# ATmegaBootloader.net
KiCad netlist of a schematic drawn in EAGLE
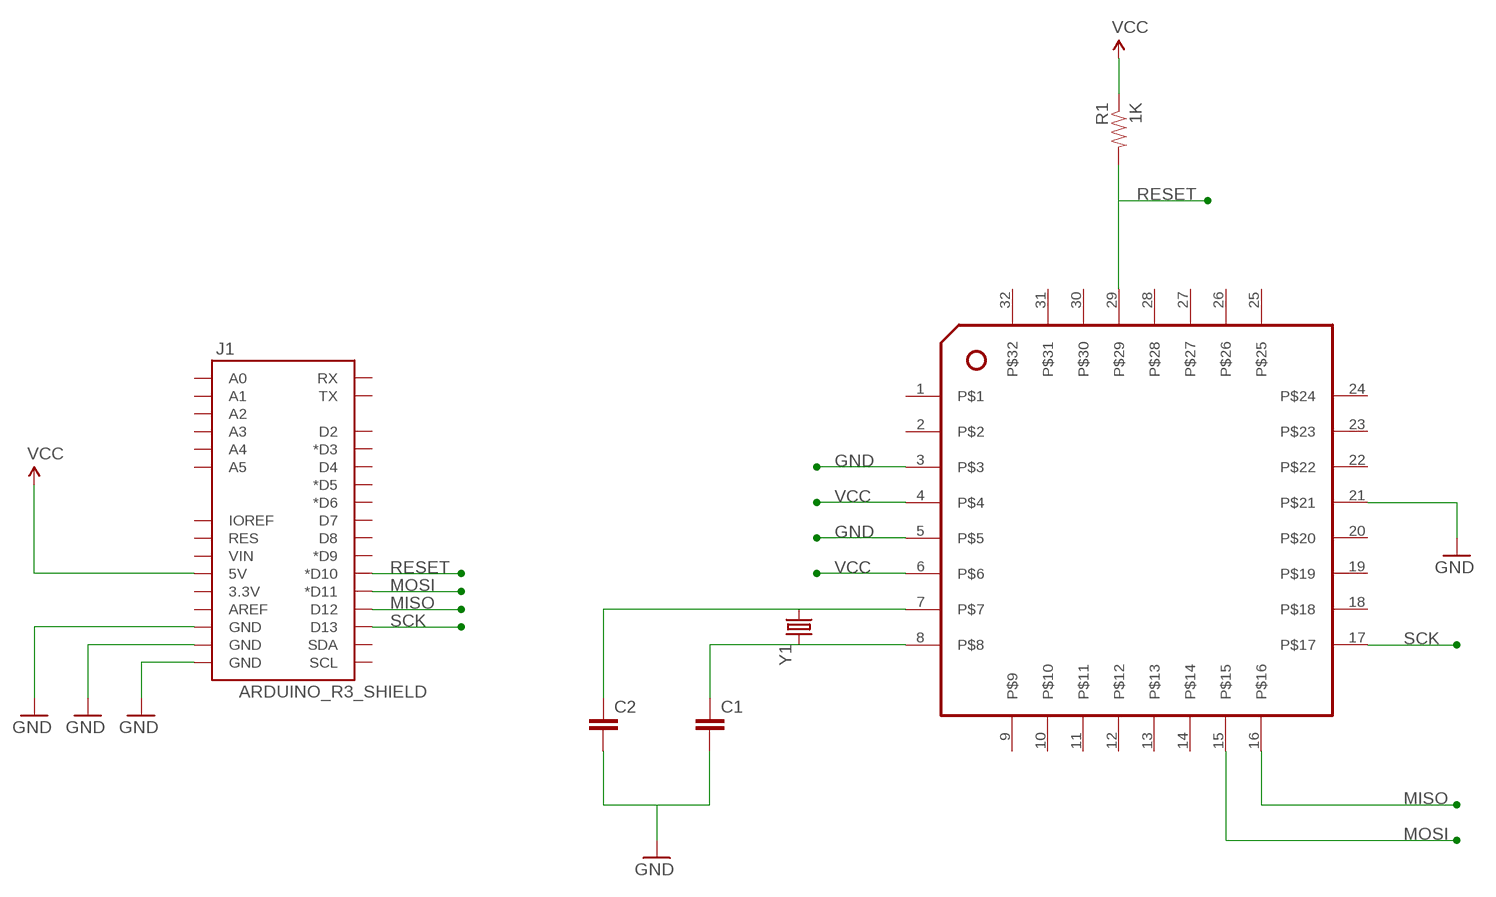
[diagram p0: schematic, sheet 1]

(export (version "E")
  (design (tool "Eeschema 10.0.6"))
  (components
    (comp (ref "C1")
      (value "0.1UF-50V-20%(PTH)KIT-EZ")
      (footprint "eagle-import:CAP-PTH-SMALL-KIT")
      (libsource (lib "eagle-import") (part "0.1UF-50V-20%(PTH)KIT-EZ"))
    )
    (comp (ref "C2")
      (value "0.1UF-50V-20%(PTH)KIT-EZ")
      (footprint "eagle-import:CAP-PTH-SMALL-KIT")
      (libsource (lib "eagle-import") (part "0.1UF-50V-20%(PTH)KIT-EZ"))
    )
    (comp (ref "J1")
      (value "ARDUINO_R3_SHIELD")
      (footprint "eagle-import:UNO_R3_SHIELD")
      (libsource (lib "eagle-import") (part "ARDUINO_R3_SHIELD"))
    )
    (comp (ref "R1")
      (value "1K")
      (footprint "eagle-import:AXIAL-0.3")
      (libsource (lib "eagle-import") (part "1KOHM-1/4W-1%(PTH)"))
    )
    (comp (ref "U$1")
      (value "ATMEGA-TQFP-BREAKOUT")
      (footprint "eagle-import:TQFP32-BREAKOUT")
      (libsource (lib "eagle-import") (part "ATMEGA-TQFP-BREAKOUT"))
    )
    (comp (ref "Y1")
      (value "CRYSTALHC49US")
      (footprint "eagle-import:HC49US")
      (libsource (lib "eagle-import") (part "CRYSTALHC49US"))
    )
  )
  (nets
    (net (code "1") (name "/MISO") (class "Default")
      (node (ref "J1") (pin "D12") (pinfunction "D12_D12") (pintype "bidirectional"))
      (node (ref "U$1") (pin "16") (pinfunction "P$16_16") (pintype "bidirectional"))
    )
    (net (code "2") (name "/MOSI") (class "Default")
      (node (ref "J1") (pin "D11") (pinfunction "*D11_D11") (pintype "bidirectional"))
      (node (ref "U$1") (pin "15") (pinfunction "P$15_15") (pintype "bidirectional"))
    )
    (net (code "3") (name "/RESET") (class "Default")
      (node (ref "J1") (pin "D10") (pinfunction "*D10_D10") (pintype "bidirectional"))
      (node (ref "R1") (pin "P$2") (pinfunction "2_P$2") (pintype "passive"))
      (node (ref "U$1") (pin "29") (pinfunction "P$29_29") (pintype "bidirectional"))
    )
    (net (code "4") (name "/SCK") (class "Default")
      (node (ref "J1") (pin "D13") (pinfunction "D13_D13") (pintype "bidirectional"))
      (node (ref "U$1") (pin "17") (pinfunction "P$17_17") (pintype "bidirectional"))
    )
    (net (code "5") (name "GND") (class "Default")
      (node (ref "C1") (pin "2") (pinfunction "2_2") (pintype "passive"))
      (node (ref "C2") (pin "2") (pinfunction "2_2") (pintype "passive"))
      (node (ref "J1") (pin "GND@0") (pinfunction "GND_GND@0") (pintype "bidirectional"))
      (node (ref "J1") (pin "GND@1") (pinfunction "GND_GND@1") (pintype "bidirectional"))
      (node (ref "J1") (pin "GND@2") (pinfunction "GND_GND@2") (pintype "bidirectional"))
      (node (ref "U$1") (pin "21") (pinfunction "P$21_21") (pintype "bidirectional"))
      (node (ref "U$1") (pin "3") (pinfunction "P$3_3") (pintype "bidirectional"))
      (node (ref "U$1") (pin "5") (pinfunction "P$5_5") (pintype "bidirectional"))
    )
    (net (code "6") (name "Net-(U$1-P$7)") (class "Default")
      (node (ref "C2") (pin "1") (pinfunction "1_1") (pintype "passive"))
      (node (ref "U$1") (pin "7") (pinfunction "P$7_7") (pintype "bidirectional"))
      (node (ref "Y1") (pin "1") (pinfunction "1_1") (pintype "passive"))
    )
    (net (code "7") (name "Net-(U$1-P$8)") (class "Default")
      (node (ref "C1") (pin "1") (pinfunction "1_1") (pintype "passive"))
      (node (ref "U$1") (pin "8") (pinfunction "P$8_8") (pintype "bidirectional"))
      (node (ref "Y1") (pin "2") (pinfunction "2_2") (pintype "passive"))
    )
    (net (code "8") (name "VCC") (class "Default")
      (node (ref "J1") (pin "5V") (pinfunction "5V_5V") (pintype "bidirectional"))
      (node (ref "R1") (pin "P$1") (pinfunction "1_P$1") (pintype "passive"))
      (node (ref "U$1") (pin "4") (pinfunction "P$4_4") (pintype "bidirectional"))
      (node (ref "U$1") (pin "6") (pinfunction "P$6_6") (pintype "bidirectional"))
    )
    (net (code "9") (name "unconnected-(J1-*D3-PadD3)") (class "Default")
      (node (ref "J1") (pin "D3") (pinfunction "*D3_D3") (pintype "bidirectional"))
    )
    (net (code "10") (name "unconnected-(J1-*D5-PadD5)") (class "Default")
      (node (ref "J1") (pin "D5") (pinfunction "*D5_D5") (pintype "bidirectional"))
    )
    (net (code "11") (name "unconnected-(J1-*D6-PadD6)") (class "Default")
      (node (ref "J1") (pin "D6") (pinfunction "*D6_D6") (pintype "bidirectional"))
    )
    (net (code "12") (name "unconnected-(J1-*D9-PadD9)") (class "Default")
      (node (ref "J1") (pin "D9") (pinfunction "*D9_D9") (pintype "bidirectional"))
    )
    (net (code "13") (name "unconnected-(J1-Pad3.3V)") (class "Default")
      (node (ref "J1") (pin "3.3V") (pinfunction "3.3V_3.3V") (pintype "bidirectional"))
    )
    (net (code "14") (name "unconnected-(J1-PadA0)") (class "Default")
      (node (ref "J1") (pin "A0") (pinfunction "A0_A0") (pintype "bidirectional"))
    )
    (net (code "15") (name "unconnected-(J1-PadA1)") (class "Default")
      (node (ref "J1") (pin "A1") (pinfunction "A1_A1") (pintype "bidirectional"))
    )
    (net (code "16") (name "unconnected-(J1-PadA2)") (class "Default")
      (node (ref "J1") (pin "A2") (pinfunction "A2_A2") (pintype "bidirectional"))
    )
    (net (code "17") (name "unconnected-(J1-PadA3)") (class "Default")
      (node (ref "J1") (pin "A3") (pinfunction "A3_A3") (pintype "bidirectional"))
    )
    (net (code "18") (name "unconnected-(J1-PadA4)") (class "Default")
      (node (ref "J1") (pin "A4") (pinfunction "A4_A4") (pintype "bidirectional"))
    )
    (net (code "19") (name "unconnected-(J1-PadA5)") (class "Default")
      (node (ref "J1") (pin "A5") (pinfunction "A5_A5") (pintype "bidirectional"))
    )
    (net (code "20") (name "unconnected-(J1-PadAREF)") (class "Default")
      (node (ref "J1") (pin "AREF") (pinfunction "AREF_AREF") (pintype "bidirectional"))
    )
    (net (code "21") (name "unconnected-(J1-PadD2)") (class "Default")
      (node (ref "J1") (pin "D2") (pinfunction "D2_D2") (pintype "bidirectional"))
    )
    (net (code "22") (name "unconnected-(J1-PadD4)") (class "Default")
      (node (ref "J1") (pin "D4") (pinfunction "D4_D4") (pintype "bidirectional"))
    )
    (net (code "23") (name "unconnected-(J1-PadD7)") (class "Default")
      (node (ref "J1") (pin "D7") (pinfunction "D7_D7") (pintype "bidirectional"))
    )
    (net (code "24") (name "unconnected-(J1-PadD8)") (class "Default")
      (node (ref "J1") (pin "D8") (pinfunction "D8_D8") (pintype "bidirectional"))
    )
    (net (code "25") (name "unconnected-(J1-PadIOREF)") (class "Default")
      (node (ref "J1") (pin "IOREF") (pinfunction "IOREF_IOREF") (pintype "bidirectional"))
    )
    (net (code "26") (name "unconnected-(J1-PadRES)") (class "Default")
      (node (ref "J1") (pin "RES") (pinfunction "RES_RES") (pintype "bidirectional"))
    )
    (net (code "27") (name "unconnected-(J1-PadRX)") (class "Default")
      (node (ref "J1") (pin "RX") (pinfunction "RX_RX") (pintype "bidirectional"))
    )
    (net (code "28") (name "unconnected-(J1-PadSCL)") (class "Default")
      (node (ref "J1") (pin "SCL") (pinfunction "SCL_SCL") (pintype "bidirectional"))
    )
    (net (code "29") (name "unconnected-(J1-PadSDA)") (class "Default")
      (node (ref "J1") (pin "SDA") (pinfunction "SDA_SDA") (pintype "bidirectional"))
    )
    (net (code "30") (name "unconnected-(J1-PadTX)") (class "Default")
      (node (ref "J1") (pin "TX") (pinfunction "TX_TX") (pintype "bidirectional"))
    )
    (net (code "31") (name "unconnected-(J1-PadVIN)") (class "Default")
      (node (ref "J1") (pin "VIN") (pinfunction "VIN_VIN") (pintype "bidirectional"))
    )
    (net (code "32") (name "unconnected-(U$1-P$1-Pad1)") (class "Default")
      (node (ref "U$1") (pin "1") (pinfunction "P$1_1") (pintype "bidirectional"))
    )
    (net (code "33") (name "unconnected-(U$1-P$2-Pad2)") (class "Default")
      (node (ref "U$1") (pin "2") (pinfunction "P$2_2") (pintype "bidirectional"))
    )
    (net (code "34") (name "unconnected-(U$1-P$9-Pad9)") (class "Default")
      (node (ref "U$1") (pin "9") (pinfunction "P$9_9") (pintype "bidirectional"))
    )
    (net (code "35") (name "unconnected-(U$1-P$10-Pad10)") (class "Default")
      (node (ref "U$1") (pin "10") (pinfunction "P$10_10") (pintype "bidirectional"))
    )
    (net (code "36") (name "unconnected-(U$1-P$11-Pad11)") (class "Default")
      (node (ref "U$1") (pin "11") (pinfunction "P$11_11") (pintype "bidirectional"))
    )
    (net (code "37") (name "unconnected-(U$1-P$12-Pad12)") (class "Default")
      (node (ref "U$1") (pin "12") (pinfunction "P$12_12") (pintype "bidirectional"))
    )
    (net (code "38") (name "unconnected-(U$1-P$13-Pad13)") (class "Default")
      (node (ref "U$1") (pin "13") (pinfunction "P$13_13") (pintype "bidirectional"))
    )
    (net (code "39") (name "unconnected-(U$1-P$14-Pad14)") (class "Default")
      (node (ref "U$1") (pin "14") (pinfunction "P$14_14") (pintype "bidirectional"))
    )
    (net (code "40") (name "unconnected-(U$1-P$18-Pad18)") (class "Default")
      (node (ref "U$1") (pin "18") (pinfunction "P$18_18") (pintype "bidirectional"))
    )
    (net (code "41") (name "unconnected-(U$1-P$19-Pad19)") (class "Default")
      (node (ref "U$1") (pin "19") (pinfunction "P$19_19") (pintype "bidirectional"))
    )
    (net (code "42") (name "unconnected-(U$1-P$20-Pad20)") (class "Default")
      (node (ref "U$1") (pin "20") (pinfunction "P$20_20") (pintype "bidirectional"))
    )
    (net (code "43") (name "unconnected-(U$1-P$22-Pad22)") (class "Default")
      (node (ref "U$1") (pin "22") (pinfunction "P$22_22") (pintype "bidirectional"))
    )
    (net (code "44") (name "unconnected-(U$1-P$23-Pad23)") (class "Default")
      (node (ref "U$1") (pin "23") (pinfunction "P$23_23") (pintype "bidirectional"))
    )
    (net (code "45") (name "unconnected-(U$1-P$24-Pad24)") (class "Default")
      (node (ref "U$1") (pin "24") (pinfunction "P$24_24") (pintype "bidirectional"))
    )
    (net (code "46") (name "unconnected-(U$1-P$25-Pad25)") (class "Default")
      (node (ref "U$1") (pin "25") (pinfunction "P$25_25") (pintype "bidirectional"))
    )
    (net (code "47") (name "unconnected-(U$1-P$26-Pad26)") (class "Default")
      (node (ref "U$1") (pin "26") (pinfunction "P$26_26") (pintype "bidirectional"))
    )
    (net (code "48") (name "unconnected-(U$1-P$27-Pad27)") (class "Default")
      (node (ref "U$1") (pin "27") (pinfunction "P$27_27") (pintype "bidirectional"))
    )
    (net (code "49") (name "unconnected-(U$1-P$28-Pad28)") (class "Default")
      (node (ref "U$1") (pin "28") (pinfunction "P$28_28") (pintype "bidirectional"))
    )
    (net (code "50") (name "unconnected-(U$1-P$30-Pad30)") (class "Default")
      (node (ref "U$1") (pin "30") (pinfunction "P$30_30") (pintype "bidirectional"))
    )
    (net (code "51") (name "unconnected-(U$1-P$31-Pad31)") (class "Default")
      (node (ref "U$1") (pin "31") (pinfunction "P$31_31") (pintype "bidirectional"))
    )
    (net (code "52") (name "unconnected-(U$1-P$32-Pad32)") (class "Default")
      (node (ref "U$1") (pin "32") (pinfunction "P$32_32") (pintype "bidirectional"))
    )
  )
)
